# Sheet2.net
KiCad netlist of a schematic drawn in Altium Designer
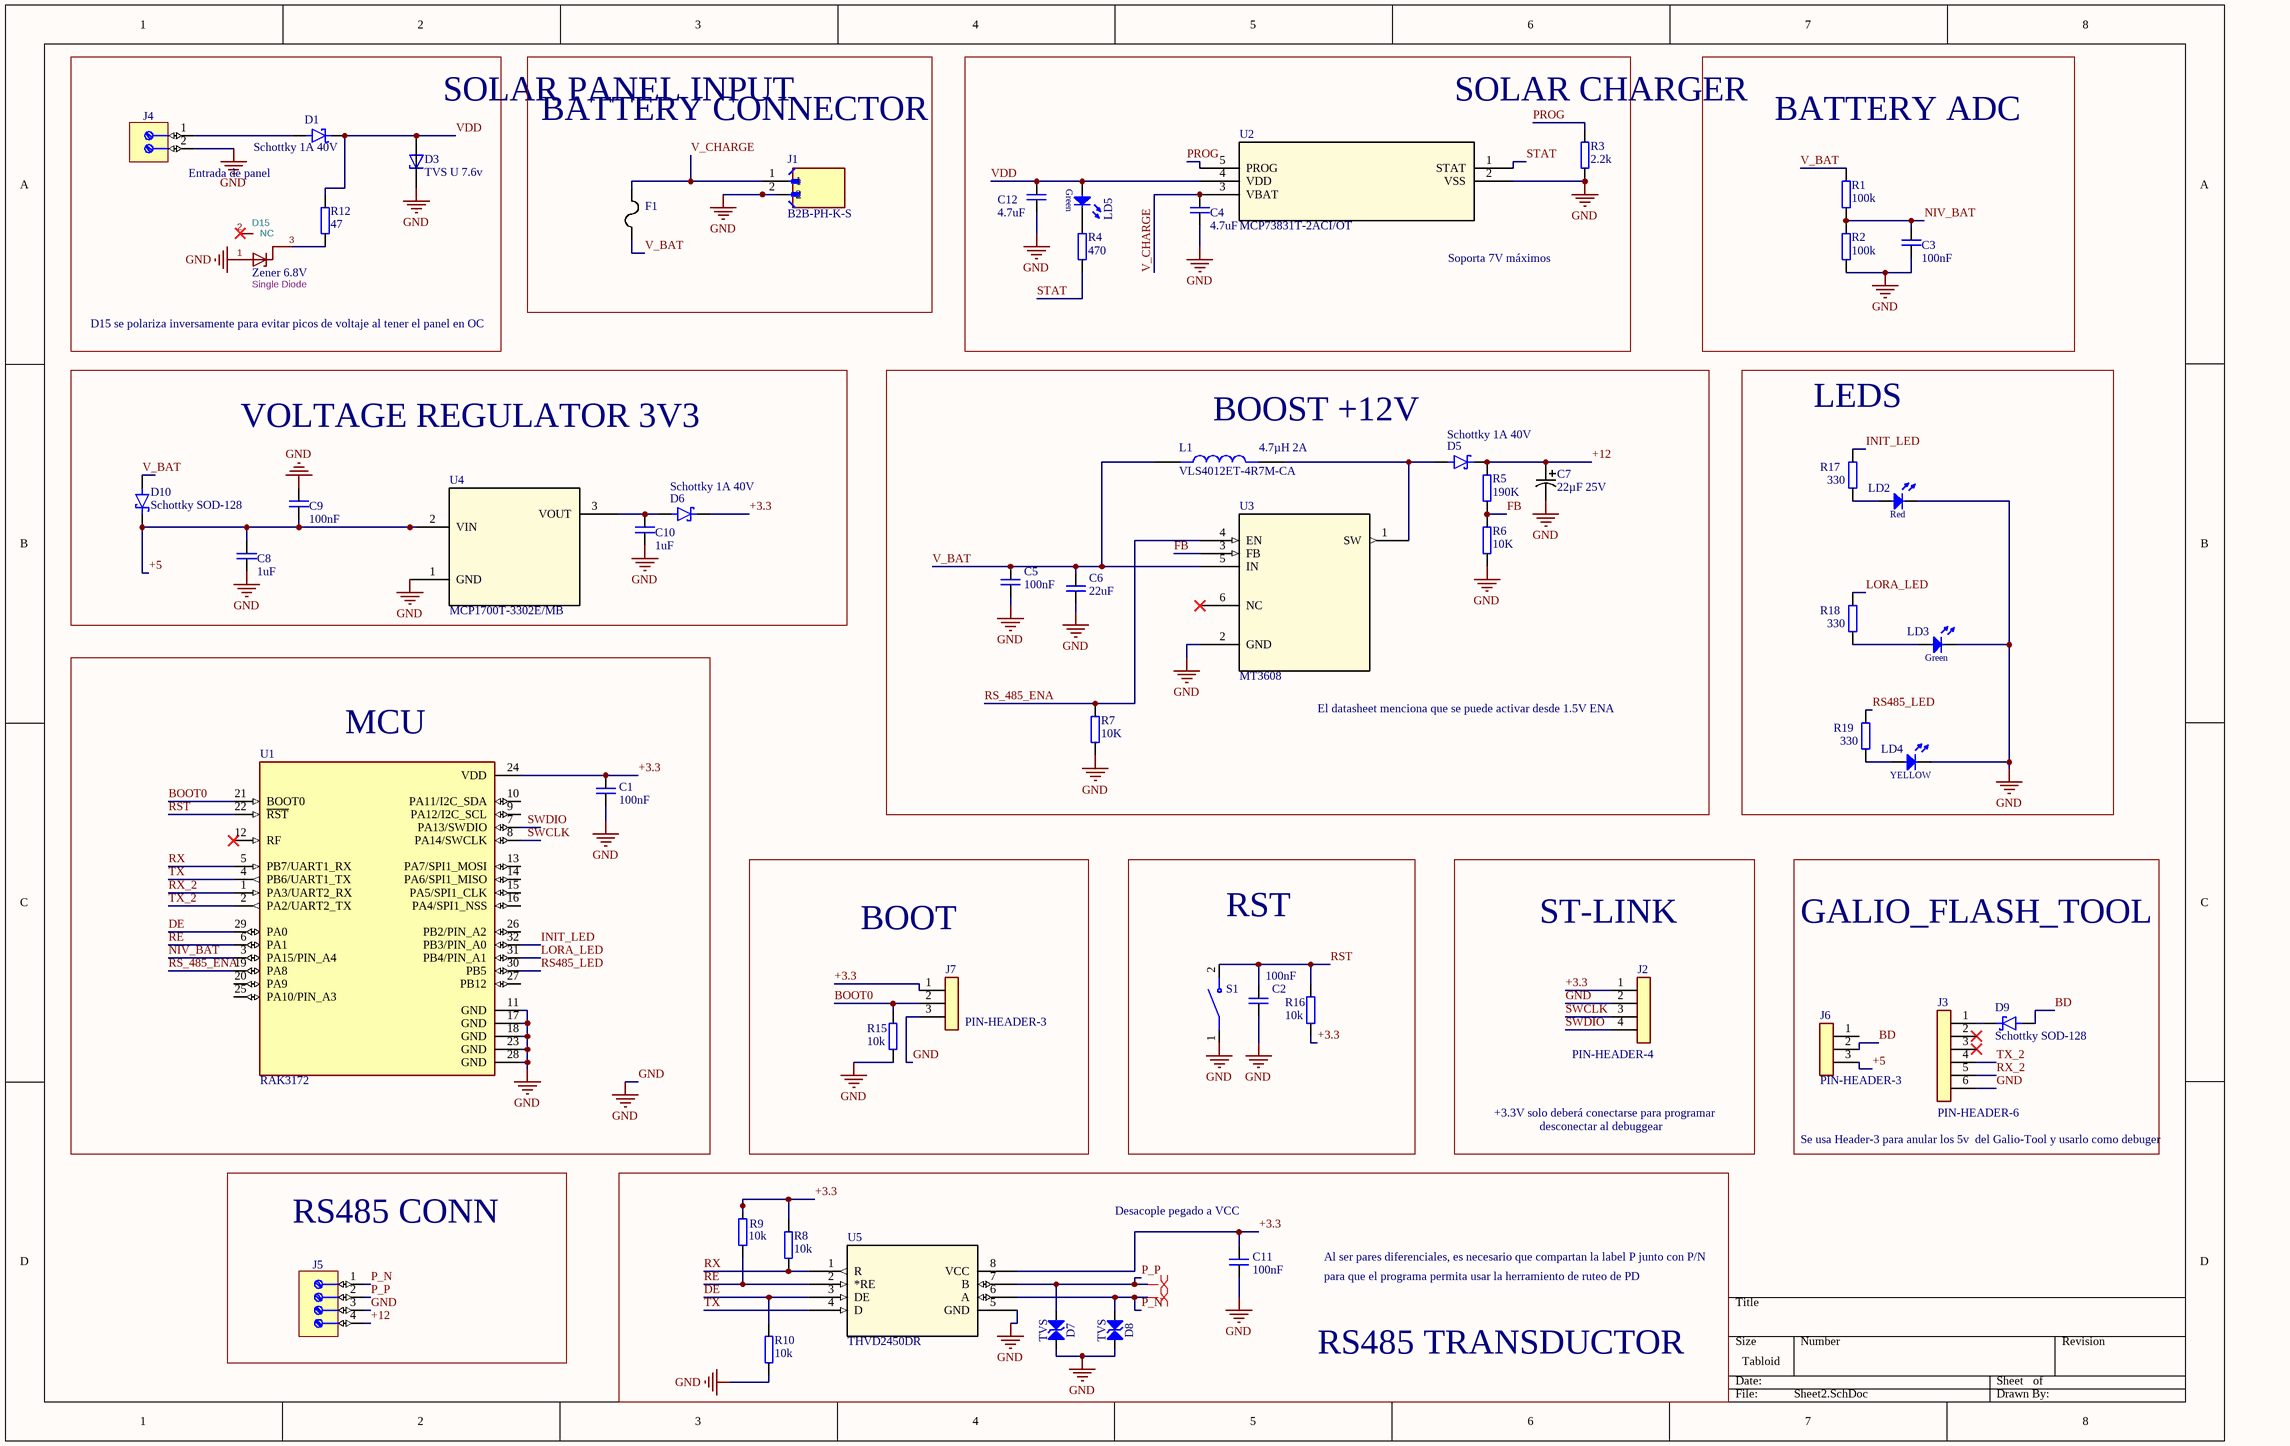
[diagram p0: Sheet2.SchDoc]

(export (version "E")
  (design (tool "Eeschema 10.0.6"))
  (components
    (comp (ref "C1")
      (value "100nF")
      (footprint "CAPC2012X110N")
      (description "CAPACITOR, 0805")
      (fields (field (name "MF") "KEMET") (field (name "MP") "C0805C125K4RACTU"))
      (libsource (lib "Galio-complete") (part "C0805C125K4RACTU"))
    )
    (comp (ref "C2")
      (value "100nF")
      (footprint "CAPC2012X110N")
      (description "CAPACITOR, 0805")
      (fields (field (name "MF") "KEMET") (field (name "MP") "C0805C125K4RACTU"))
      (libsource (lib "Galio-complete") (part "C0805C125K4RACTU"))
    )
    (comp (ref "C3")
      (value "100nF")
      (footprint "CAPC2012X110N")
      (description "CAPACITOR, 0805")
      (fields (field (name "MF") "KEMET") (field (name "MP") "C0805C125K4RACTU"))
      (libsource (lib "Galio-complete") (part "C0805C125K4RACTU"))
    )
    (comp (ref "C4")
      (value "4.7uF")
      (footprint "CAPC2012X110N")
      (description "CAPACITOR, 0805")
      (fields (field (name "MF") "KEMET") (field (name "MP") "C0805C125K4RACTU"))
      (libsource (lib "") (part "C0805C125K4RACTU_1"))
    )
    (comp (ref "C5")
      (value "100nF")
      (footprint "CAPC2012X110N")
      (description "CAPACITOR, 0805")
      (fields (field (name "MF") "KEMET") (field (name "MP") "C0805C125K4RACTU"))
      (libsource (lib "Galio-complete") (part "C0805C125K4RACTU"))
    )
    (comp (ref "C6")
      (value "22uF")
      (footprint "CAPC2012X110N")
      (description "CAPACITOR, 0805")
      (fields (field (name "MF") "KEMET") (field (name "MP") "C0805C125K4RACTU"))
      (libsource (lib "Galio-complete") (part "C0805C125K4RACTU"))
    )
    (comp (ref "C7")
      (value "22µF 25V")
      (footprint "CAP_EEFK_C_PAN")
      (description "Capacitor electrolítico aluminio SMD")
      (fields
        (field (name "MANUFACTURER_PART_NUMBER") "EEE-FK1E220AR")
        (field (name "COPYRIGHT") "Copyright (C) 2026 Ultra Librarian. All rights reserved.")
      )
      (libsource (lib "Galio-complete") (part "EEE-FK1E220AR"))
    )
    (comp (ref "C8")
      (value "1uF")
      (footprint "CAPC2012X110N")
      (description "CAPACITOR, 0805")
      (fields (field (name "MF") "KEMET") (field (name "MP") "C0805C125K4RACTU"))
      (libsource (lib "Galio-complete") (part "C0805C125K4RACTU"))
    )
    (comp (ref "C9")
      (value "100nF")
      (footprint "CAPC2012X110N")
      (description "CAPACITOR, 0805")
      (fields (field (name "MF") "KEMET") (field (name "MP") "C0805C125K4RACTU"))
      (libsource (lib "Galio-complete") (part "C0805C125K4RACTU"))
    )
    (comp (ref "C10")
      (value "1uF")
      (footprint "CAPC2012X110N")
      (description "CAPACITOR, 0805")
      (fields (field (name "MF") "KEMET") (field (name "MP") "C0805C125K4RACTU"))
      (libsource (lib "Galio-complete") (part "C0805C125K4RACTU"))
    )
    (comp (ref "C11")
      (value "100nF")
      (footprint "CAPC2012X110N")
      (description "CAPACITOR, 0805")
      (fields (field (name "MF") "KEMET") (field (name "MP") "C0805C125K4RACTU"))
      (libsource (lib "Galio-complete") (part "C0805C125K4RACTU"))
    )
    (comp (ref "C12")
      (value "4.7uF")
      (footprint "CAPC2012X110N")
      (description "CAPACITOR, 0805")
      (fields (field (name "MF") "KEMET") (field (name "MP") "C0805C125K4RACTU"))
      (libsource (lib "") (part "C0805C125K4RACTU_1"))
    )
    (comp (ref "D1")
      (value "Schottky 1A 40V")
      (footprint "SODFL4725X110N")
      (description "Diode Schottky 40V 2A Surface Mount SOD-128/CFP5")
      (fields (field (name "MF") "Nexperia USA") (field (name "MP") "PMEG4020ETP,115"))
      (libsource (lib "Galio-complete") (part "PMEG4020ETP,115"))
    )
    (comp (ref "D3")
      (value "TVS U 7.6v")
      (footprint "DIOM4325X250N")
      (description "11 TVS Diode Surface Mount DO-214AC (SMA)")
      (fields (field (name "MF") "Bourns") (field (name "MP") "SMAJ11A"))
      (libsource (lib "Galio-complete") (part "SMAJ11A"))
    )
    (comp (ref "D5")
      (value "Schottky 1A 40V")
      (footprint "SODFL4725X110N")
      (description "Diode Schottky 40V 2A Surface Mount SOD-128/CFP5")
      (fields (field (name "MF") "Nexperia USA") (field (name "MP") "PMEG4020ETP,115"))
      (libsource (lib "Galio-complete") (part "PMEG4020ETP,115"))
    )
    (comp (ref "D6")
      (value "Schottky 1A 40V")
      (footprint "SODFL4725X110N")
      (description "Diode Schottky 40V 2A Surface Mount SOD-128/CFP5")
      (fields (field (name "MF") "Nexperia USA") (field (name "MP") "PMEG4020ETP,115"))
      (libsource (lib "Galio-complete") (part "PMEG4020ETP,115"))
    )
    (comp (ref "D7")
      (value "TVS")
      (footprint "DIOM5126X229N")
      (description "Transient Voltage Suppressor Diode (Bi-Directional)")
      (libsource (lib "Galio-complete") (part "Diode TVS Bi-Directional"))
    )
    (comp (ref "D8")
      (value "TVS")
      (footprint "DIOM5126X229N")
      (description "Transient Voltage Suppressor Diode (Bi-Directional)")
      (libsource (lib "Galio-complete") (part "Diode TVS Bi-Directional"))
    )
    (comp (ref "D9")
      (value "Schottky SOD-128")
      (footprint "SODFL4725X110N")
      (description "Diode Schottky 40V 2A Surface Mount SOD-128/CFP5")
      (fields (field (name "MF") "Nexperia USA") (field (name "MP") "PMEG4020ETP,115"))
      (libsource (lib "Galio-complete") (part "PMEG4020ETP,115"))
    )
    (comp (ref "D10")
      (value "Schottky SOD-128")
      (footprint "SODFL4725X110N")
      (description "Diode Schottky 40V 2A Surface Mount SOD-128/CFP5")
      (fields (field (name "MF") "Nexperia USA") (field (name "MP") "PMEG4020ETP,115"))
      (libsource (lib "Galio-complete") (part "PMEG4020ETP,115"))
    )
    (comp (ref "D15")
      (value "Zener 6.8V")
      (footprint "SOT-23")
      (fields (field (name "ALTIUM_VALUE") "Single Diode"))
      (libsource (lib "Galio-complete") (part "Zener-Diode_NC"))
    )
    (comp (ref "F1")
      (value "~")
      (footprint "FUSE_MF-MSMF07524-2_BRN")
      (description "Fuse")
      (fields
        (field (name "MANUFACTURER_PART_NUMBER") "MF-MSMF075/24-2")
        (field (name "COPYRIGHT") "Copyright (C) 2026 Ultra Librarian. All rights reserved.")
      )
      (libsource (lib "Galio-complete") (part "MF-MSMF07524-2"))
    )
    (comp (ref "J1")
      (value "B2B-PH-K-S")
      (footprint "JST_B2B-PH-K-S")
      (description "Connector Header Through Hole 2 position 0.079 (2.00mm)")
      (fields (field (name "MF") "JST Sales America Inc."))
      (libsource (lib "Galio-connectors") (part "B2B-PH-K-S"))
    )
    (comp (ref "J2")
      (value "PIN-HEADER-4")
      (footprint "PIN-HEADER-4-MALE")
      (fields (field (name "MP") "MTSW-104-06-T-S-100"))
      (libsource (lib "Galio-connectors") (part "PIN-HEADER-4"))
    )
    (comp (ref "J3")
      (value "PIN-HEADER-6")
      (footprint "PIN-HEADER-6-FEMALE")
      (fields (field (name "MP") "MTSW-106-06-T-S-100"))
      (libsource (lib "Galio-connectors") (part "PIN-HEADER-6"))
    )
    (comp (ref "J4")
      (value "TRT2")
      (footprint "TRT_2_KF301")
      (description "Terminal Block, 2 Positions, Screw Connection")
      (libsource (lib "Galio-connectors") (part "TRT_2"))
    )
    (comp (ref "J5")
      (value "TRT4")
      (footprint "TRT_4_ KF301")
      (description "TRT_4")
      (libsource (lib "Galio-connectors") (part "TRT_4"))
    )
    (comp (ref "J6")
      (value "PIN-HEADER-3")
      (footprint "PIN-HEADER-3-MALE")
      (fields (field (name "MP") "MTSW-103-06-T-S-190"))
      (libsource (lib "Galio-connectors") (part "PIN-HEADER-3"))
    )
    (comp (ref "J7")
      (value "PIN-HEADER-3")
      (footprint "PIN-HEADER-3-MALE")
      (fields (field (name "MP") "MTSW-103-06-T-S-190"))
      (libsource (lib "") (part "PIN-HEADER-3_1"))
    )
    (comp (ref "L1")
      (value "VLS4012ET-4R7M-CA")
      (footprint "IND_VLS4012ET-4R7M-CA")
      (description "4.7 µH Shielded Drum Core, Wirewound Inductor 1.9 A 118mOhm Max Nonstandard")
      (fields (field (name "MF") "TDK"))
      (libsource (lib "Galio-complete") (part "VLS4012ET-4R7M-CA"))
    )
    (comp (ref "LD2")
      (value "~")
      (footprint "LEDC2012X70N")
      (description "LED Red 0805")
      (libsource (lib "Galio-complete") (part "LED Red 0805"))
    )
    (comp (ref "LD3")
      (value "~")
      (footprint "LEDC2012X70N")
      (description "LED Green 0805")
      (libsource (lib "Galio-complete") (part "LED Green 0805"))
    )
    (comp (ref "LD4")
      (value "~")
      (footprint "LEDC2012X70N")
      (description "LED Yellow 0805")
      (libsource (lib "Galio-complete") (part "LED Yellow 0805"))
    )
    (comp (ref "LD5")
      (value "~")
      (footprint "LEDC2012X70N")
      (description "LED Green 0805")
      (libsource (lib "Galio-complete") (part "LED Green 0805"))
    )
    (comp (ref "R1")
      (value "100k")
      (footprint "RESC2013X84N")
      (libsource (lib "Galio-complete") (part "RES"))
    )
    (comp (ref "R2")
      (value "100k")
      (footprint "RESC2013X84N")
      (libsource (lib "Galio-complete") (part "RES"))
    )
    (comp (ref "R3")
      (value "2.2k")
      (footprint "RESC2013X84N")
      (libsource (lib "Galio-complete") (part "RES"))
    )
    (comp (ref "R4") (value "470") (footprint "RESC2013X84N") (libsource (lib "Galio-complete") (part "RES")))
    (comp (ref "R5")
      (value "190K")
      (footprint "RESC2013X84N")
      (libsource (lib "Galio-complete") (part "RES"))
    )
    (comp (ref "R6") (value "10K") (footprint "RESC2013X84N") (libsource (lib "Galio-complete") (part "RES")))
    (comp (ref "R7") (value "10K") (footprint "RESC2013X84N") (libsource (lib "Galio-complete") (part "RES")))
    (comp (ref "R8") (value "10k") (footprint "RESC2013X84N") (libsource (lib "Galio-complete") (part "RES")))
    (comp (ref "R9") (value "10k") (footprint "RESC2013X84N") (libsource (lib "Galio-complete") (part "RES")))
    (comp (ref "R10")
      (value "10k")
      (footprint "RESC2013X84N")
      (libsource (lib "Galio-complete") (part "RES"))
    )
    (comp (ref "R12") (value "47") (footprint "RESC2013X84N") (libsource (lib "Galio-complete") (part "RES")))
    (comp (ref "R15")
      (value "10k")
      (footprint "RESC2013X84N")
      (libsource (lib "Galio-complete") (part "RES"))
    )
    (comp (ref "R16")
      (value "10k")
      (footprint "RESC2013X84N")
      (libsource (lib "Galio-complete") (part "RES"))
    )
    (comp (ref "R17")
      (value "330")
      (footprint "RESC2013X84N")
      (libsource (lib "Galio-complete") (part "RES"))
    )
    (comp (ref "R18")
      (value "330")
      (footprint "RESC2013X84N")
      (libsource (lib "Galio-complete") (part "RES"))
    )
    (comp (ref "R19")
      (value "330")
      (footprint "RESC2013X84N")
      (libsource (lib "Galio-complete") (part "RES"))
    )
    (comp (ref "S1")
      (value "~")
      (footprint "SWITCH-SMD-4x3mm")
      (fields (field (name "MF") "Xunpu") (field (name "MP") "TS-1088-AR02016"))
      (libsource (lib "Galio-complete") (part "SWITCH-SMD-4x3mm"))
    )
    (comp (ref "U1")
      (value "RAK3172")
      (footprint "XCVR_RAK3172")
      (fields (field (name "MF") "Shenzhen RAKwireless Technology Co.,Ltd."))
      (libsource (lib "Galio-modules") (part "RAK3172"))
    )
    (comp (ref "U2")
      (value "MCP73831T-2ACI/OT")
      (footprint "SOT-23-5_MC_MCH-M")
      (description "Series Single-Cell Li-Ion/Li-Polymer Battery Charge Controller")
      (fields (field (name "COPYRIGHT") "Copyright (C) 2025 Ultra Librarian. All rights reserved."))
      (libsource (lib "Galio-complete") (part "MCP73831T-2ACIOT"))
    )
    (comp (ref "U3")
      (value "MT3608")
      (footprint "TSOT23-6SOT23-6_AER")
      (description "DC-DC step-up")
      (fields (field (name "COPYRIGHT") "Copyright (C) 2025 Ultra Librarian. All rights reserved."))
      (libsource (lib "Galio-complete") (part "MT3608"))
    )
    (comp (ref "U4")
      (value "MCP1700T-3302E/MB")
      (footprint "SOT-89_3MC_MCH")
      (description "Linear Voltage Regulators")
      (fields (field (name "COPYRIGHT") "Copyright (C) 2026 Ultra Librarian. All rights reserved."))
      (libsource (lib "Galio-complete") (part "MCP1700T-3302EMB"))
    )
    (comp (ref "U5")
      (value "THVD2450DR")
      (footprint "SOIC8-N_MC")
      (description "Transceiver Half RS422, RS485 SOIC-8")
      (fields (field (name "COPYRIGHT") "Copyright (C) 2025 Ultra Librarian. All rights reserved."))
      (libsource (lib "Galio-complete") (part "THVD2450DR"))
    )
  )
  (nets
    (net (code "1") (name "/+3.3") (class "Default")
      (node (ref "C1") (pin "2") (pinfunction "2_2") (pintype "passive"))
      (node (ref "C11") (pin "2") (pinfunction "2_2") (pintype "passive"))
      (node (ref "D6") (pin "1") (pinfunction "K_1") (pintype "passive"))
      (node (ref "J2") (pin "1") (pintype "passive"))
      (node (ref "J7") (pin "1") (pintype "passive"))
      (node (ref "R16") (pin "1") (pinfunction "1_1") (pintype "passive"))
      (node (ref "R8") (pin "2") (pinfunction "2_2") (pintype "passive"))
      (node (ref "R9") (pin "2") (pinfunction "2_2") (pintype "passive"))
      (node (ref "U1") (pin "24") (pinfunction "VDD_24") (pintype "power_in"))
      (node (ref "U5") (pin "8") (pinfunction "VCC_8") (pintype "power_in"))
    )
    (net (code "2") (name "/+5") (class "Default")
      (node (ref "C8") (pin "2") (pinfunction "2_2") (pintype "passive"))
      (node (ref "C9") (pin "1") (pinfunction "1_1") (pintype "passive"))
      (node (ref "D10") (pin "1") (pinfunction "K_1") (pintype "passive"))
      (node (ref "J6") (pin "3") (pintype "passive"))
      (node (ref "U4") (pin "2") (pinfunction "VIN_2") (pintype "passive"))
    )
    (net (code "3") (name "/+12") (class "Default")
      (node (ref "C7") (pin "1") (pinfunction "1_1") (pintype "passive"))
      (node (ref "D5") (pin "1") (pinfunction "K_1") (pintype "passive"))
      (node (ref "J5") (pin "4") (pinfunction "4_4") (pintype "bidirectional"))
      (node (ref "R5") (pin "2") (pinfunction "2_2") (pintype "passive"))
    )
    (net (code "4") (name "/BD") (class "Default")
      (node (ref "D9") (pin "2") (pinfunction "A_2") (pintype "passive"))
      (node (ref "J6") (pin "2") (pintype "passive"))
    )
    (net (code "5") (name "/BOOT0") (class "Default")
      (node (ref "J7") (pin "2") (pintype "passive"))
      (node (ref "R15") (pin "2") (pinfunction "2_2") (pintype "passive"))
      (node (ref "U1") (pin "21") (pinfunction "BOOT0_21") (pintype "input"))
    )
    (net (code "6") (name "/DE") (class "Default")
      (node (ref "R10") (pin "2") (pinfunction "2_2") (pintype "passive"))
      (node (ref "U1") (pin "29") (pinfunction "PA0_29") (pintype "bidirectional"))
      (node (ref "U5") (pin "3") (pinfunction "DE_3") (pintype "input"))
    )
    (net (code "7") (name "/FB") (class "Default")
      (node (ref "R5") (pin "1") (pinfunction "1_1") (pintype "passive"))
      (node (ref "R6") (pin "2") (pinfunction "2_2") (pintype "passive"))
      (node (ref "U3") (pin "3") (pinfunction "FB_3") (pintype "input"))
    )
    (net (code "8") (name "/INIT_LED") (class "Default")
      (node (ref "R17") (pin "2") (pinfunction "2_2") (pintype "passive"))
      (node (ref "U1") (pin "32") (pinfunction "PB3/PIN_A0_32") (pintype "bidirectional"))
    )
    (net (code "9") (name "/LORA_LED") (class "Default")
      (node (ref "R18") (pin "2") (pinfunction "2_2") (pintype "passive"))
      (node (ref "U1") (pin "31") (pinfunction "PB4/PIN_A1_31") (pintype "bidirectional"))
    )
    (net (code "10") (name "/NIV_BAT") (class "Default")
      (node (ref "C3") (pin "2") (pinfunction "2_2") (pintype "passive"))
      (node (ref "R1") (pin "1") (pinfunction "1_1") (pintype "passive"))
      (node (ref "R2") (pin "2") (pinfunction "2_2") (pintype "passive"))
      (node (ref "U1") (pin "3") (pinfunction "PA15/PIN_A4_3") (pintype "bidirectional"))
    )
    (net (code "11") (name "/PROG") (class "Default")
      (node (ref "R3") (pin "2") (pinfunction "2_2") (pintype "passive"))
      (node (ref "U2") (pin "5") (pinfunction "PROG_5") (pintype "passive"))
    )
    (net (code "12") (name "/P_N") (class "Default")
      (node (ref "D8") (pin "2") (pinfunction "A_2") (pintype "passive"))
      (node (ref "J5") (pin "1") (pinfunction "1_1") (pintype "bidirectional"))
      (node (ref "U5") (pin "6") (pinfunction "A_6") (pintype "bidirectional"))
    )
    (net (code "13") (name "/P_P") (class "Default")
      (node (ref "D7") (pin "2") (pinfunction "A_2") (pintype "passive"))
      (node (ref "J5") (pin "2") (pinfunction "2_2") (pintype "bidirectional"))
      (node (ref "U5") (pin "7") (pinfunction "B_7") (pintype "bidirectional"))
    )
    (net (code "14") (name "/RE") (class "Default")
      (node (ref "R9") (pin "1") (pinfunction "1_1") (pintype "passive"))
      (node (ref "U1") (pin "6") (pinfunction "PA1_6") (pintype "bidirectional"))
      (node (ref "U5") (pin "2") (pinfunction "*RE_2") (pintype "input"))
    )
    (net (code "15") (name "/RS485_LED") (class "Default")
      (node (ref "R19") (pin "2") (pinfunction "2_2") (pintype "passive"))
      (node (ref "U1") (pin "30") (pinfunction "PB5_30") (pintype "bidirectional"))
    )
    (net (code "16") (name "/RST") (class "Default")
      (node (ref "C2") (pin "2") (pinfunction "2_2") (pintype "passive"))
      (node (ref "R16") (pin "2") (pinfunction "2_2") (pintype "passive"))
      (node (ref "S1") (pin "2") (pinfunction "2_2") (pintype "passive"))
      (node (ref "U1") (pin "22") (pinfunction "~{RST}_22") (pintype "input"))
    )
    (net (code "17") (name "/RS_485_ENA") (class "Default")
      (node (ref "R7") (pin "2") (pinfunction "2_2") (pintype "passive"))
      (node (ref "U1") (pin "19") (pinfunction "PA8_19") (pintype "bidirectional"))
      (node (ref "U3") (pin "4") (pinfunction "EN_4") (pintype "input"))
    )
    (net (code "18") (name "/RX") (class "Default")
      (node (ref "R8") (pin "1") (pinfunction "1_1") (pintype "passive"))
      (node (ref "U1") (pin "5") (pinfunction "PB7/UART1_RX_5") (pintype "input"))
      (node (ref "U5") (pin "1") (pinfunction "R_1") (pintype "output"))
    )
    (net (code "19") (name "/RX_2") (class "Default")
      (node (ref "J3") (pin "5") (pintype "passive"))
      (node (ref "U1") (pin "1") (pinfunction "PA3/UART2_RX_1") (pintype "input"))
    )
    (net (code "20") (name "/STAT") (class "Default")
      (node (ref "R4") (pin "1") (pinfunction "1_1") (pintype "passive"))
      (node (ref "U2") (pin "1") (pinfunction "STAT_1") (pintype "passive"))
    )
    (net (code "21") (name "/SWCLK") (class "Default")
      (node (ref "J2") (pin "3") (pintype "passive"))
      (node (ref "U1") (pin "8") (pinfunction "PA14/SWCLK_8") (pintype "bidirectional"))
    )
    (net (code "22") (name "/SWDIO") (class "Default")
      (node (ref "J2") (pin "4") (pintype "passive"))
      (node (ref "U1") (pin "7") (pinfunction "PA13/SWDIO_7") (pintype "bidirectional"))
    )
    (net (code "23") (name "/TX") (class "Default")
      (node (ref "U1") (pin "4") (pinfunction "PB6/UART1_TX_4") (pintype "output"))
      (node (ref "U5") (pin "4") (pinfunction "D_4") (pintype "input"))
    )
    (net (code "24") (name "/TX_2") (class "Default")
      (node (ref "J3") (pin "4") (pintype "passive"))
      (node (ref "U1") (pin "2") (pinfunction "PA2/UART2_TX_2") (pintype "output"))
    )
    (net (code "25") (name "/VDD") (class "Default")
      (node (ref "C12") (pin "2") (pinfunction "2_2") (pintype "passive"))
      (node (ref "D1") (pin "1") (pinfunction "K_1") (pintype "passive"))
      (node (ref "D3") (pin "A") (pinfunction "A_A") (pintype "passive"))
      (node (ref "LD5") (pin "2") (pinfunction "A_2") (pintype "passive"))
      (node (ref "R12") (pin "2") (pinfunction "2_2") (pintype "passive"))
      (node (ref "U2") (pin "4") (pinfunction "VDD_4") (pintype "passive"))
    )
    (net (code "26") (name "/V_BAT") (class "Default")
      (node (ref "C5") (pin "2") (pinfunction "2_2") (pintype "passive"))
      (node (ref "C6") (pin "2") (pinfunction "2_2") (pintype "passive"))
      (node (ref "D10") (pin "2") (pinfunction "A_2") (pintype "passive"))
      (node (ref "F1") (pin "1") (pinfunction "1_1") (pintype "passive"))
      (node (ref "L1") (pin "1") (pinfunction "1_1") (pintype "passive"))
      (node (ref "R1") (pin "2") (pinfunction "2_2") (pintype "passive"))
      (node (ref "U3") (pin "5") (pinfunction "IN_5") (pintype "power_in"))
    )
    (net (code "27") (name "/V_CHARGE") (class "Default")
      (node (ref "C4") (pin "2") (pinfunction "2_2") (pintype "passive"))
      (node (ref "F1") (pin "2") (pinfunction "2_2") (pintype "passive"))
      (node (ref "J1") (pin "1") (pinfunction "1_1") (pintype "passive"))
      (node (ref "U2") (pin "3") (pinfunction "VBAT_3") (pintype "passive"))
    )
    (net (code "28") (name "GND") (class "Default")
      (node (ref "C1") (pin "1") (pinfunction "1_1") (pintype "passive"))
      (node (ref "C10") (pin "1") (pinfunction "1_1") (pintype "passive"))
      (node (ref "C11") (pin "1") (pinfunction "1_1") (pintype "passive"))
      (node (ref "C12") (pin "1") (pinfunction "1_1") (pintype "passive"))
      (node (ref "C2") (pin "1") (pinfunction "1_1") (pintype "passive"))
      (node (ref "C3") (pin "1") (pinfunction "1_1") (pintype "passive"))
      (node (ref "C4") (pin "1") (pinfunction "1_1") (pintype "passive"))
      (node (ref "C5") (pin "1") (pinfunction "1_1") (pintype "passive"))
      (node (ref "C6") (pin "1") (pinfunction "1_1") (pintype "passive"))
      (node (ref "C7") (pin "2") (pinfunction "2_2") (pintype "passive"))
      (node (ref "C8") (pin "1") (pinfunction "1_1") (pintype "passive"))
      (node (ref "C9") (pin "2") (pinfunction "2_2") (pintype "passive"))
      (node (ref "D15") (pin "1") (pinfunction "A_1") (pintype "passive"))
      (node (ref "D3") (pin "C") (pinfunction "C_C") (pintype "passive"))
      (node (ref "D7") (pin "1") (pinfunction "C_1") (pintype "passive"))
      (node (ref "D8") (pin "1") (pinfunction "C_1") (pintype "passive"))
      (node (ref "J1") (pin "2") (pinfunction "2_2") (pintype "passive"))
      (node (ref "J2") (pin "2") (pintype "passive"))
      (node (ref "J3") (pin "6") (pintype "passive"))
      (node (ref "J4") (pin "2") (pinfunction "2_2") (pintype "bidirectional"))
      (node (ref "J5") (pin "3") (pinfunction "3_3") (pintype "bidirectional"))
      (node (ref "J7") (pin "3") (pintype "passive"))
      (node (ref "LD2") (pin "1") (pinfunction "C_1") (pintype "passive"))
      (node (ref "LD3") (pin "1") (pinfunction "C_1") (pintype "passive"))
      (node (ref "LD4") (pin "1") (pinfunction "C_1") (pintype "passive"))
      (node (ref "R10") (pin "1") (pinfunction "1_1") (pintype "passive"))
      (node (ref "R15") (pin "1") (pinfunction "1_1") (pintype "passive"))
      (node (ref "R2") (pin "1") (pinfunction "1_1") (pintype "passive"))
      (node (ref "R3") (pin "1") (pinfunction "1_1") (pintype "passive"))
      (node (ref "R6") (pin "1") (pinfunction "1_1") (pintype "passive"))
      (node (ref "R7") (pin "1") (pinfunction "1_1") (pintype "passive"))
      (node (ref "S1") (pin "1") (pinfunction "1_1") (pintype "passive"))
      (node (ref "U1") (pin "11") (pinfunction "GND_11") (pintype "power_in"))
      (node (ref "U1") (pin "17") (pinfunction "GND_17") (pintype "power_in"))
      (node (ref "U1") (pin "18") (pinfunction "GND_18") (pintype "power_in"))
      (node (ref "U1") (pin "23") (pinfunction "GND_23") (pintype "power_in"))
      (node (ref "U1") (pin "28") (pinfunction "GND_28") (pintype "power_in"))
      (node (ref "U2") (pin "2") (pinfunction "VSS_2") (pintype "passive"))
      (node (ref "U3") (pin "2") (pinfunction "GND_2") (pintype "power_in"))
      (node (ref "U4") (pin "1") (pinfunction "GND_1") (pintype "passive"))
      (node (ref "U5") (pin "5") (pinfunction "GND_5") (pintype "power_in"))
    )
    (net (code "29") (name "Net-(D1-A)") (class "Default")
      (node (ref "D1") (pin "2") (pinfunction "A_2") (pintype "passive"))
      (node (ref "J4") (pin "1") (pinfunction "1_1") (pintype "bidirectional"))
    )
    (net (code "30") (name "Net-(D5-A)") (class "Default")
      (node (ref "D5") (pin "2") (pinfunction "A_2") (pintype "passive"))
      (node (ref "L1") (pin "2") (pinfunction "2_2") (pintype "passive"))
      (node (ref "U3") (pin "1") (pinfunction "SW_1") (pintype "output"))
    )
    (net (code "31") (name "Net-(D6-A)") (class "Default")
      (node (ref "C10") (pin "2") (pinfunction "2_2") (pintype "passive"))
      (node (ref "D6") (pin "2") (pinfunction "A_2") (pintype "passive"))
      (node (ref "U4") (pin "3") (pinfunction "VOUT_3") (pintype "passive"))
    )
    (net (code "32") (name "Net-(D9-K)") (class "Default")
      (node (ref "D9") (pin "1") (pinfunction "K_1") (pintype "passive"))
      (node (ref "J3") (pin "1") (pintype "passive"))
    )
    (net (code "33") (name "Net-(D15-C)") (class "Default")
      (node (ref "D15") (pin "3") (pinfunction "C_3") (pintype "passive"))
      (node (ref "R12") (pin "1") (pinfunction "1_1") (pintype "passive"))
    )
    (net (code "34") (name "Net-(LD2-A)") (class "Default")
      (node (ref "LD2") (pin "2") (pinfunction "A_2") (pintype "passive"))
      (node (ref "R17") (pin "1") (pinfunction "1_1") (pintype "passive"))
    )
    (net (code "35") (name "Net-(LD3-A)") (class "Default")
      (node (ref "LD3") (pin "2") (pinfunction "A_2") (pintype "passive"))
      (node (ref "R18") (pin "1") (pinfunction "1_1") (pintype "passive"))
    )
    (net (code "36") (name "Net-(LD4-A)") (class "Default")
      (node (ref "LD4") (pin "2") (pinfunction "A_2") (pintype "passive"))
      (node (ref "R19") (pin "1") (pinfunction "1_1") (pintype "passive"))
    )
    (net (code "37") (name "Net-(LD5-C)") (class "Default")
      (node (ref "LD5") (pin "1") (pinfunction "C_1") (pintype "passive"))
      (node (ref "R4") (pin "2") (pinfunction "2_2") (pintype "passive"))
    )
    (net (code "38") (name "unconnected-(D15-NC-Pad2)") (class "Default")
      (node (ref "D15") (pin "2") (pinfunction "NC_2") (pintype "passive+no_connect"))
    )
    (net (code "39") (name "unconnected-(J3-Pad2)") (class "Default")
      (node (ref "J3") (pin "2") (pintype "passive+no_connect"))
    )
    (net (code "40") (name "unconnected-(J3-Pad3)") (class "Default")
      (node (ref "J3") (pin "3") (pintype "passive+no_connect"))
    )
    (net (code "41") (name "unconnected-(J6-Pad1)") (class "Default")
      (node (ref "J6") (pin "1") (pintype "passive"))
    )
    (net (code "42") (name "unconnected-(U1-PA4{slash}SPI1_NSS-Pad16)") (class "Default")
      (node (ref "U1") (pin "16") (pinfunction "PA4/SPI1_NSS_16") (pintype "bidirectional"))
    )
    (net (code "43") (name "unconnected-(U1-PA5{slash}SPI1_CLK-Pad15)") (class "Default")
      (node (ref "U1") (pin "15") (pinfunction "PA5/SPI1_CLK_15") (pintype "bidirectional"))
    )
    (net (code "44") (name "unconnected-(U1-PA6{slash}SPI1_MISO-Pad14)") (class "Default")
      (node (ref "U1") (pin "14") (pinfunction "PA6/SPI1_MISO_14") (pintype "bidirectional"))
    )
    (net (code "45") (name "unconnected-(U1-PA7{slash}SPI1_MOSI-Pad13)") (class "Default")
      (node (ref "U1") (pin "13") (pinfunction "PA7/SPI1_MOSI_13") (pintype "bidirectional"))
    )
    (net (code "46") (name "unconnected-(U1-PA9-Pad20)") (class "Default")
      (node (ref "U1") (pin "20") (pinfunction "PA9_20") (pintype "bidirectional"))
    )
    (net (code "47") (name "unconnected-(U1-PA10{slash}PIN_A3-Pad25)") (class "Default")
      (node (ref "U1") (pin "25") (pinfunction "PA10/PIN_A3_25") (pintype "bidirectional"))
    )
    (net (code "48") (name "unconnected-(U1-PA11{slash}I2C_SDA-Pad10)") (class "Default")
      (node (ref "U1") (pin "10") (pinfunction "PA11/I2C_SDA_10") (pintype "bidirectional"))
    )
    (net (code "49") (name "unconnected-(U1-PA12{slash}I2C_SCL-Pad9)") (class "Default")
      (node (ref "U1") (pin "9") (pinfunction "PA12/I2C_SCL_9") (pintype "bidirectional"))
    )
    (net (code "50") (name "unconnected-(U1-PB2{slash}PIN_A2-Pad26)") (class "Default")
      (node (ref "U1") (pin "26") (pinfunction "PB2/PIN_A2_26") (pintype "bidirectional"))
    )
    (net (code "51") (name "unconnected-(U1-PB12-Pad27)") (class "Default")
      (node (ref "U1") (pin "27") (pinfunction "PB12_27") (pintype "bidirectional"))
    )
    (net (code "52") (name "unconnected-(U1-RF-Pad12)") (class "Default")
      (node (ref "U1") (pin "12") (pinfunction "RF_12") (pintype "input+no_connect"))
    )
    (net (code "53") (name "unconnected-(U3-NC-Pad6)") (class "Default")
      (node (ref "U3") (pin "6") (pinfunction "NC_6") (pintype "passive+no_connect"))
    )
  )
)
